# 5-ThermoHygroSensor.net
KiCad netlist of a schematic drawn in Altium Designer
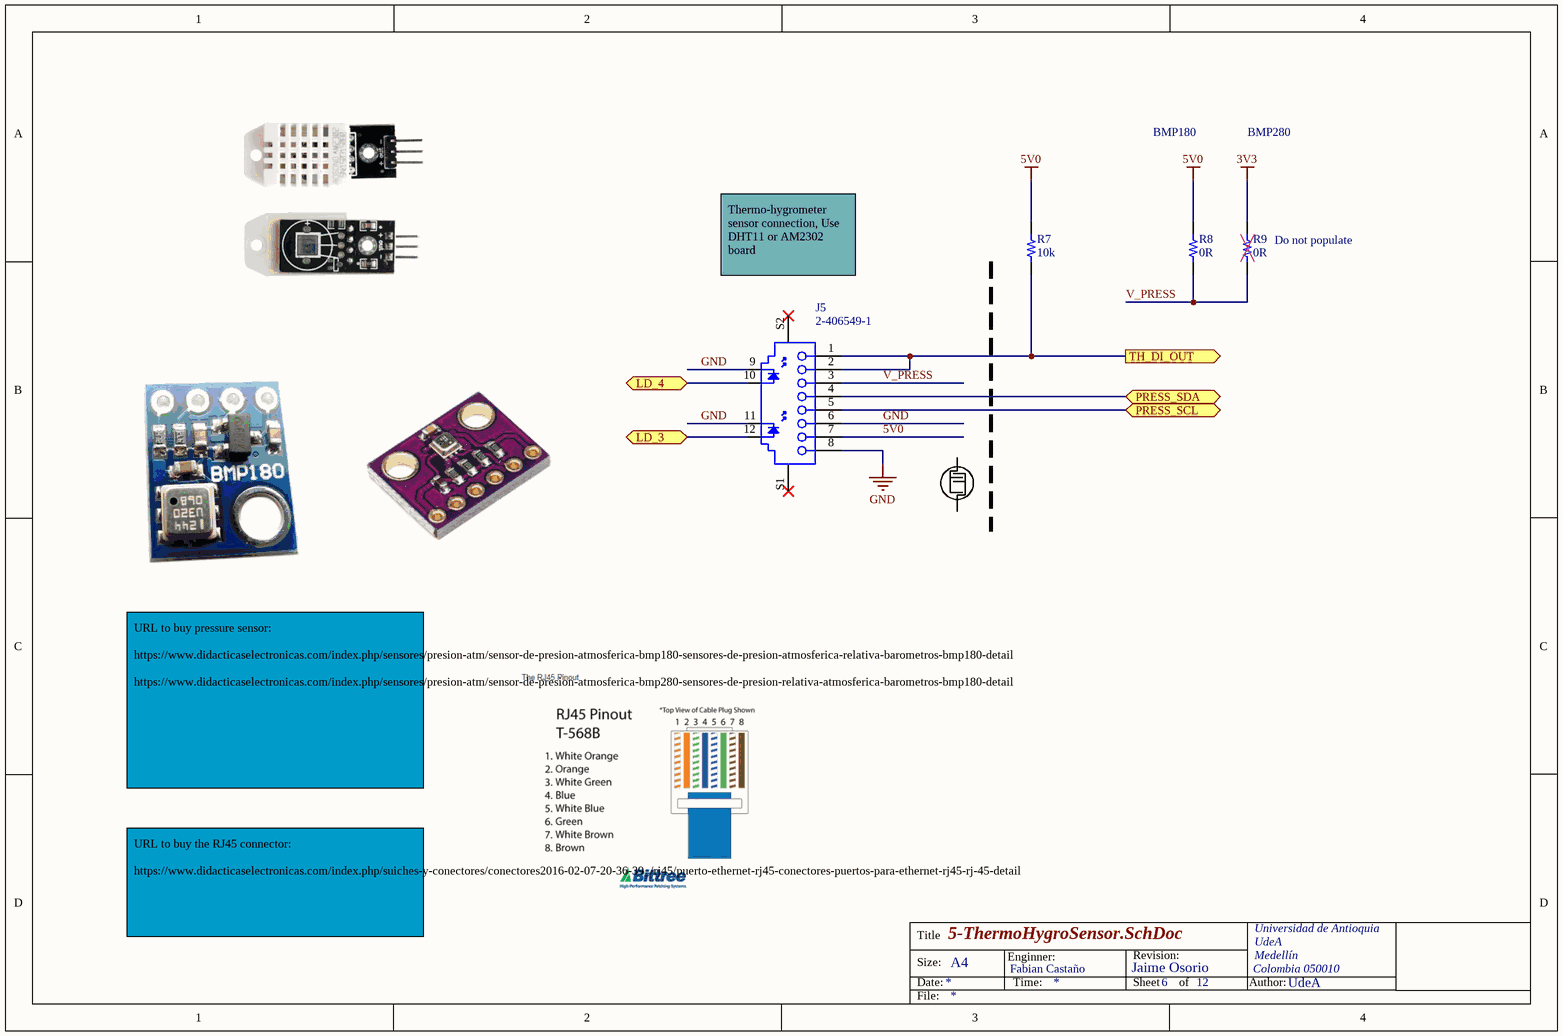
[diagram p0: 5-ThermoHygroSensor.SchDoc]

(export (version "E")
  (design (tool "Eeschema 10.0.6"))
  (components
    (comp (ref "J5")
      (value "2-406549-1")
      (footprint "TECO-2-406549-1_V")
      (description "RJ45 Connector, Pitch 1.016 mm, 8 Position, Height 14.22 mm, Tail Length 3.18 mm, RoHS, Tray")
      (fields (field (name "MANUFACTURER") "TE Connectivity"))
      (libsource (lib "Altium Content Vault") (part "RJ45-12-2SHLD_A"))
    )
    (comp (ref "R7")
      (value "10k")
      (footprint "RES 0805_2012")
      (description "RES SMD 1.47K OHM 1% 1/8W 0805")
      (fields (field (name "PART NUMBER") "RC0805FR-071K47L") (field (name "MANUFACTURER") "Yageo"))
      (libsource (lib "Celestial Altium Library - altium_library") (part "Resistor"))
    )
    (comp (ref "R8")
      (value "0R")
      (footprint "RES 0805_2012")
      (description "RES SMD 1.47K OHM 1% 1/8W 0805")
      (fields (field (name "PART NUMBER") "RC0805FR-071K47L") (field (name "MANUFACTURER") "Yageo"))
      (libsource (lib "Celestial Altium Library - altium_library") (part "Resistor"))
    )
    (comp (ref "R9")
      (value "0R")
      (footprint "RES 0805_2012")
      (description "RES SMD 1.47K OHM 1% 1/8W 0805")
      (fields (field (name "PART NUMBER") "RC0805FR-071K47L") (field (name "MANUFACTURER") "Yageo"))
      (libsource (lib "Celestial Altium Library - altium_library") (part "Resistor"))
    )
  )
  (nets
    (net (code "1") (name "/LD_3") (class "Default")
      (node (ref "J5") (pin "12") (pinfunction "12_12") (pintype "passive"))
    )
    (net (code "2") (name "/LD_4") (class "Default")
      (node (ref "J5") (pin "10") (pinfunction "10_10") (pintype "passive"))
    )
    (net (code "3") (name "/PRESS_SCL") (class "Default")
      (node (ref "J5") (pin "5") (pinfunction "5_5") (pintype "passive"))
    )
    (net (code "4") (name "/PRESS_SDA") (class "Default")
      (node (ref "J5") (pin "4") (pinfunction "4_4") (pintype "passive"))
    )
    (net (code "5") (name "/TH_DI_OUT") (class "Default")
      (node (ref "J5") (pin "1") (pinfunction "1_1") (pintype "passive"))
      (node (ref "J5") (pin "2") (pinfunction "2_2") (pintype "passive"))
      (node (ref "R7") (pin "1") (pinfunction "1_1") (pintype "passive"))
    )
    (net (code "6") (name "/V_PRESS") (class "Default")
      (node (ref "J5") (pin "3") (pinfunction "3_3") (pintype "passive"))
      (node (ref "R8") (pin "1") (pinfunction "1_1") (pintype "passive"))
      (node (ref "R9") (pin "1") (pinfunction "1_1") (pintype "passive"))
    )
    (net (code "7") (name "3V3") (class "Default")
      (node (ref "R9") (pin "2") (pinfunction "2_2") (pintype "passive"))
    )
    (net (code "8") (name "5V0") (class "Default")
      (node (ref "J5") (pin "7") (pinfunction "7_7") (pintype "passive"))
      (node (ref "R7") (pin "2") (pinfunction "2_2") (pintype "passive"))
      (node (ref "R8") (pin "2") (pinfunction "2_2") (pintype "passive"))
    )
    (net (code "9") (name "GND") (class "Default")
      (node (ref "J5") (pin "11") (pinfunction "11_11") (pintype "passive"))
      (node (ref "J5") (pin "6") (pinfunction "6_6") (pintype "passive"))
      (node (ref "J5") (pin "8") (pinfunction "8_8") (pintype "passive"))
      (node (ref "J5") (pin "9") (pinfunction "9_9") (pintype "passive"))
    )
    (net (code "10") (name "unconnected-(J5-PadS1)") (class "Default")
      (node (ref "J5") (pin "S1") (pinfunction "S1_S1") (pintype "passive+no_connect"))
    )
    (net (code "11") (name "unconnected-(J5-PadS2)") (class "Default")
      (node (ref "J5") (pin "S2") (pinfunction "S2_S2") (pintype "passive+no_connect"))
    )
  )
)
